# Main.net
KiCad netlist of a schematic drawn in Altium Designer
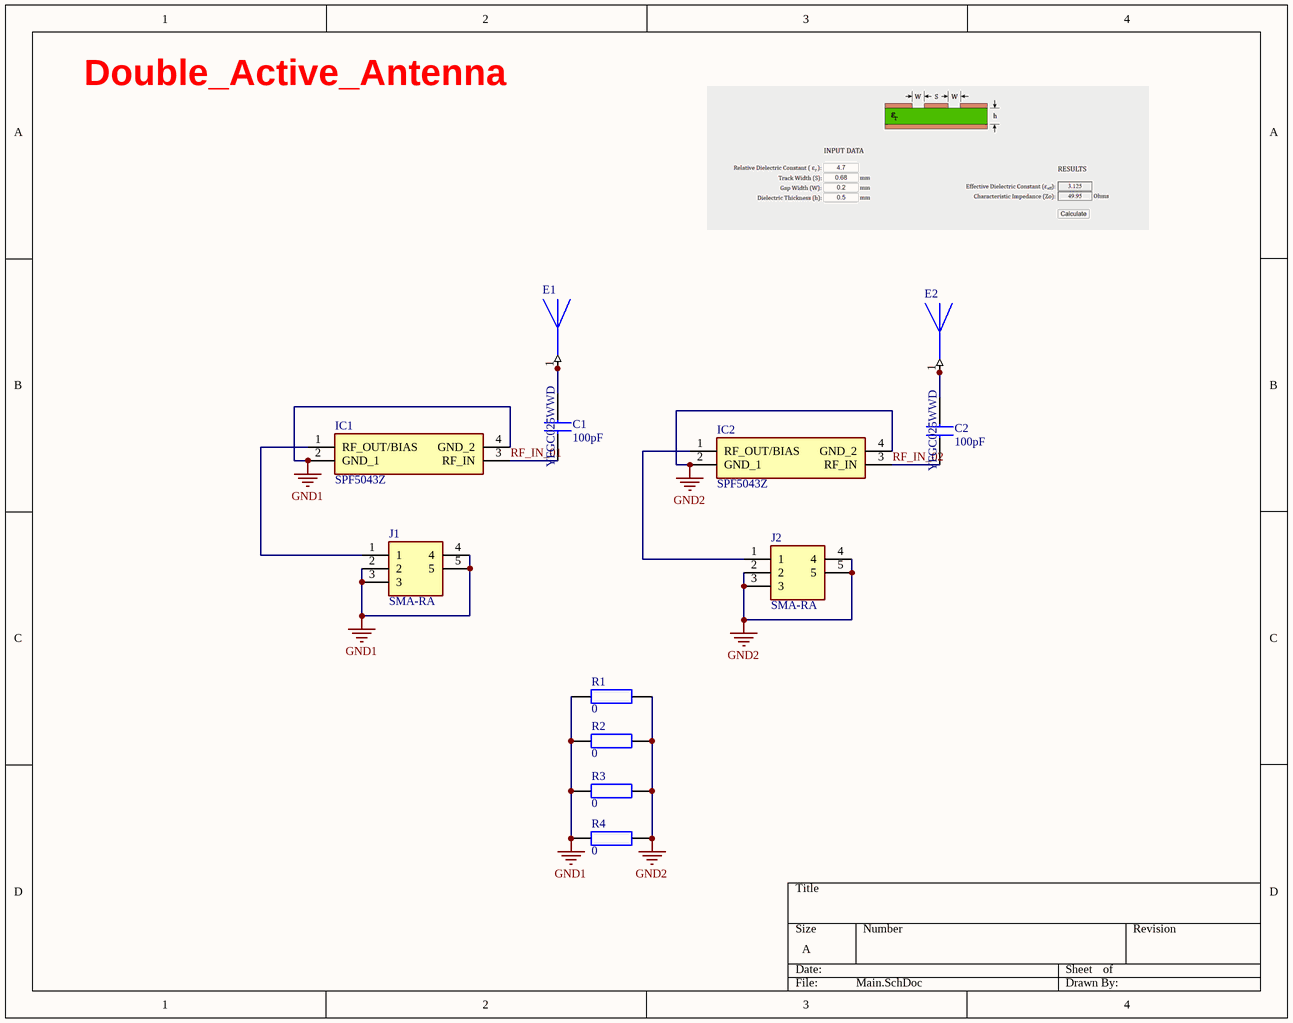
[diagram p0: Main.SchDoc]

(export (version "E")
  (design (tool "Eeschema 10.0.6"))
  (components
    (comp (ref "C1")
      (value "100pF")
      (footprint "SamacSys:GRM1885C1H101JA01D")
      (description "Capacitor")
      (fields
        (field (name "MANUFACTURER_PART_NUMBER") "GRM1885C1H101JA01D")
        (field (name "MOUSER PART NUMBER") "81-GRM39C101J50")
      )
      (libsource (lib "*") (part "GRM1885C1H101JA01D"))
    )
    (comp (ref "C2")
      (value "100pF")
      (footprint "SamacSys:GRM1885C1H101JA01D")
      (description "Capacitor")
      (fields
        (field (name "MANUFACTURER_PART_NUMBER") "GRM1885C1H101JA01D")
        (field (name "MOUSER PART NUMBER") "81-GRM39C101J50")
      )
      (libsource (lib "*") (part "GRM1885C1H101JA01D"))
    )
    (comp (ref "E1")
      (value "YFGC025WWD")
      (footprint "XDCR_YFGC025WWD")
      (libsource (lib "LNA") (part "YFGC025WWD"))
    )
    (comp (ref "E2")
      (value "YFGC025WWD")
      (footprint "XDCR_YFGC025WWD")
      (libsource (lib "LNA") (part "YFGC025WWD"))
    )
    (comp (ref "IC1")
      (value "SPF5043Z")
      (footprint "SamacSys:SPF5043Z")
      (description "Integrated Circuit")
      (fields (field (name "MOUSER PART NUMBER") "772-SPF5043Z"))
      (libsource (lib "*") (part "SPF5043Z"))
    )
    (comp (ref "IC2")
      (value "SPF5043Z")
      (footprint "SamacSys:SPF5043Z")
      (description "Integrated Circuit")
      (fields (field (name "MOUSER PART NUMBER") "772-SPF5043Z"))
      (libsource (lib "*") (part "SPF5043Z"))
    )
    (comp (ref "J1")
      (value "SMA-RA")
      (footprint "SamacSys:132135")
      (description "Connector")
      (fields
        (field (name "MANUFACTURER_PART_NUMBER") "132135")
        (field (name "MOUSER PART NUMBER") "523-132135")
      )
      (libsource (lib "*") (part "132135"))
    )
    (comp (ref "J2")
      (value "SMA-RA")
      (footprint "SamacSys:132135")
      (description "Connector")
      (fields
        (field (name "MANUFACTURER_PART_NUMBER") "132135")
        (field (name "MOUSER PART NUMBER") "523-132135")
      )
      (libsource (lib "*") (part "132135"))
    )
    (comp (ref "R1")
      (value "0")
      (footprint "RESC0805X05N")
      (description "The resistors have 2PIN in AXIAL and SMD models.\r\nAll wattage include in.")
      (libsource (lib "HiroNegarParsMainLib") (part "Resistor2P"))
    )
    (comp (ref "R2")
      (value "0")
      (footprint "RESC0805X05N")
      (description "The resistors have 2PIN in AXIAL and SMD models.\r\nAll wattage include in.")
      (libsource (lib "HiroNegarParsMainLib") (part "Resistor2P"))
    )
    (comp (ref "R3")
      (value "0")
      (footprint "RESC0805X05N")
      (description "The resistors have 2PIN in AXIAL and SMD models.\r\nAll wattage include in.")
      (libsource (lib "HiroNegarParsMainLib") (part "Resistor2P"))
    )
    (comp (ref "R4")
      (value "0")
      (footprint "RESC0805X05N")
      (description "The resistors have 2PIN in AXIAL and SMD models.\r\nAll wattage include in.")
      (libsource (lib "HiroNegarParsMainLib") (part "Resistor2P"))
    )
  )
  (nets
    (net (code "1") (name "/RF_IN_01") (class "Default")
      (node (ref "C1") (pin "1") (pinfunction "1_1") (pintype "passive"))
      (node (ref "IC1") (pin "3") (pinfunction "RF_IN_3") (pintype "passive"))
    )
    (net (code "2") (name "/RF_IN_02") (class "Default")
      (node (ref "C2") (pin "1") (pinfunction "1_1") (pintype "passive"))
      (node (ref "IC2") (pin "3") (pinfunction "RF_IN_3") (pintype "passive"))
    )
    (net (code "3") (name "GND1") (class "Default")
      (node (ref "IC1") (pin "2") (pinfunction "GND_1_2") (pintype "passive"))
      (node (ref "IC1") (pin "4") (pinfunction "GND_2_4") (pintype "passive"))
      (node (ref "J1") (pin "2") (pinfunction "2_2") (pintype "passive"))
      (node (ref "J1") (pin "3") (pinfunction "3_3") (pintype "passive"))
      (node (ref "J1") (pin "4") (pinfunction "4_4") (pintype "passive"))
      (node (ref "J1") (pin "5") (pinfunction "5_5") (pintype "passive"))
      (node (ref "R1") (pin "1") (pinfunction "1_1") (pintype "passive"))
      (node (ref "R2") (pin "1") (pinfunction "1_1") (pintype "passive"))
      (node (ref "R3") (pin "1") (pinfunction "1_1") (pintype "passive"))
      (node (ref "R4") (pin "1") (pinfunction "1_1") (pintype "passive"))
    )
    (net (code "4") (name "GND2") (class "Default")
      (node (ref "IC2") (pin "2") (pinfunction "GND_1_2") (pintype "passive"))
      (node (ref "IC2") (pin "4") (pinfunction "GND_2_4") (pintype "passive"))
      (node (ref "J2") (pin "2") (pinfunction "2_2") (pintype "passive"))
      (node (ref "J2") (pin "3") (pinfunction "3_3") (pintype "passive"))
      (node (ref "J2") (pin "4") (pinfunction "4_4") (pintype "passive"))
      (node (ref "J2") (pin "5") (pinfunction "5_5") (pintype "passive"))
      (node (ref "R1") (pin "2") (pinfunction "2_2") (pintype "passive"))
      (node (ref "R2") (pin "2") (pinfunction "2_2") (pintype "passive"))
      (node (ref "R3") (pin "2") (pinfunction "2_2") (pintype "passive"))
      (node (ref "R4") (pin "2") (pinfunction "2_2") (pintype "passive"))
    )
    (net (code "5") (name "Net-(E1-FEED)") (class "Default")
      (node (ref "C1") (pin "2") (pinfunction "2_2") (pintype "passive"))
      (node (ref "E1") (pin "1") (pinfunction "FEED_1") (pintype "input"))
    )
    (net (code "6") (name "Net-(E2-FEED)") (class "Default")
      (node (ref "C2") (pin "2") (pinfunction "2_2") (pintype "passive"))
      (node (ref "E2") (pin "1") (pinfunction "FEED_1") (pintype "input"))
    )
    (net (code "7") (name "Net-(IC1-RF_OUT{slash}BIAS)") (class "Default")
      (node (ref "IC1") (pin "1") (pinfunction "RF_OUT/BIAS_1") (pintype "passive"))
      (node (ref "J1") (pin "1") (pinfunction "1_1") (pintype "passive"))
    )
    (net (code "8") (name "Net-(IC2-RF_OUT{slash}BIAS)") (class "Default")
      (node (ref "IC2") (pin "1") (pinfunction "RF_OUT/BIAS_1") (pintype "passive"))
      (node (ref "J2") (pin "1") (pinfunction "1_1") (pintype "passive"))
    )
  )
)
